# ShiftRegV1_3.net
KiCad netlist of a schematic drawn in EasyEDA
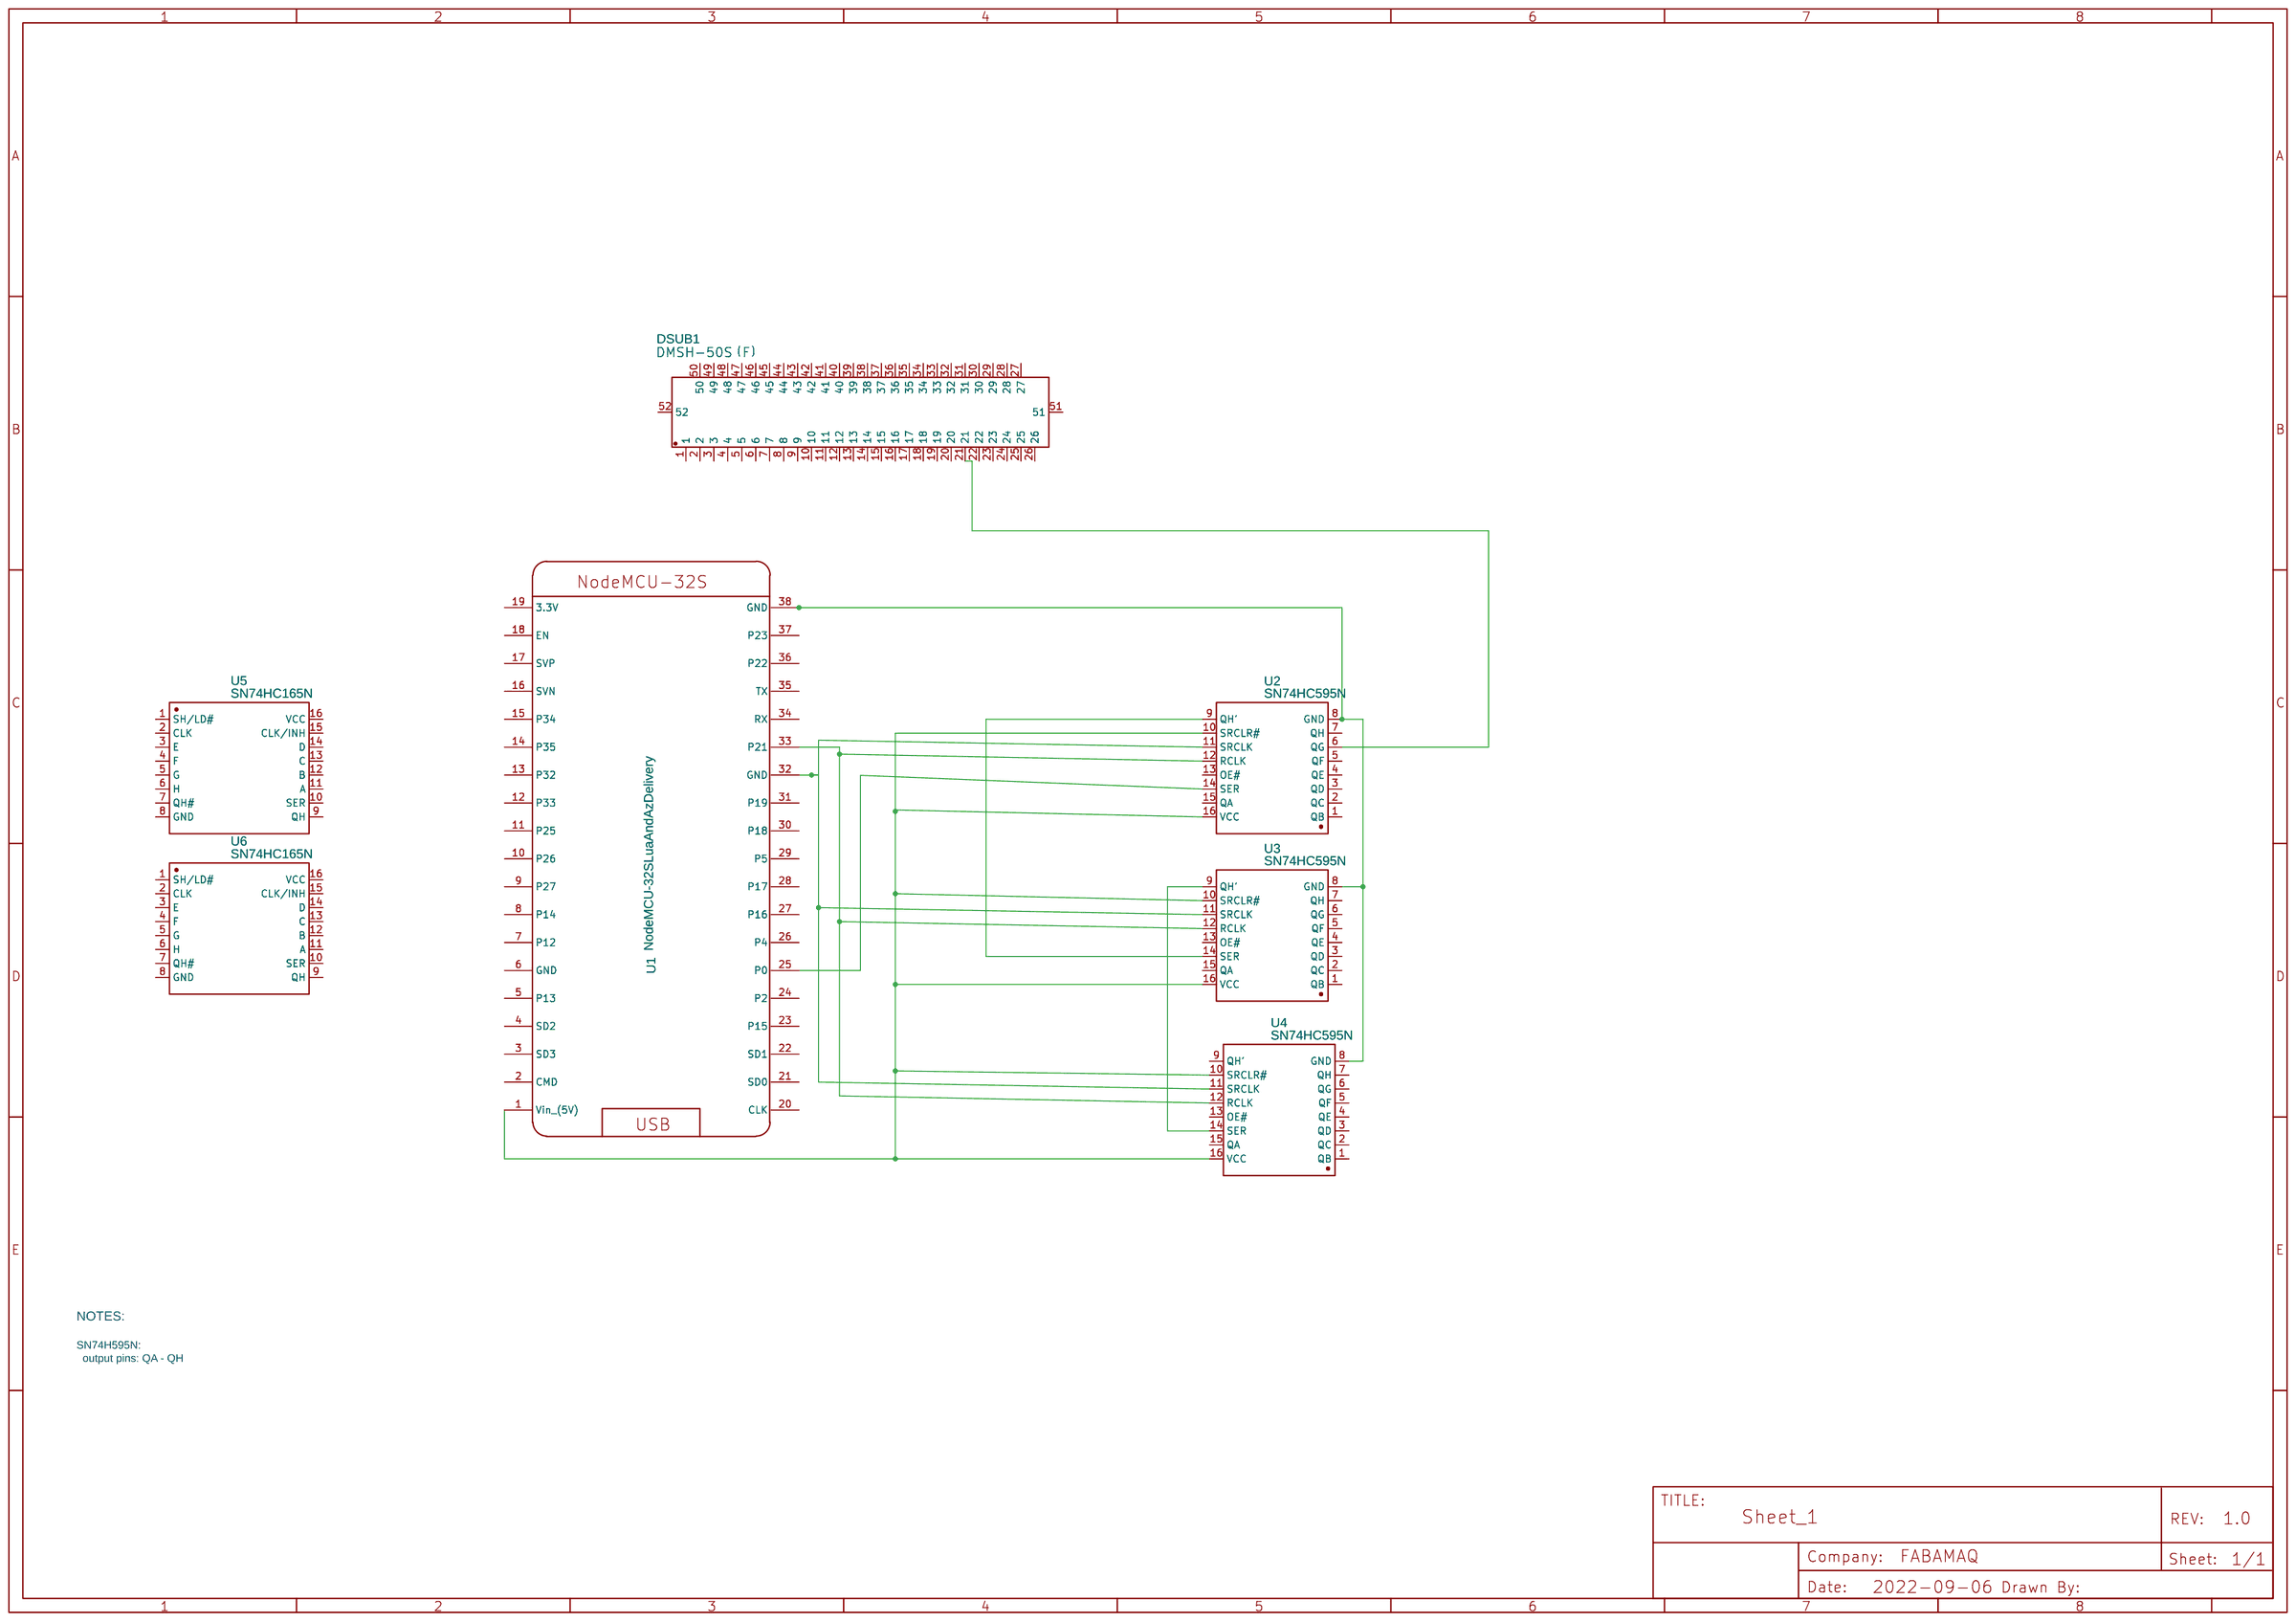
[diagram p0: schematic sheet]

(export (version "E")
  (design (tool "Eeschema 10.0.6"))
  (components
    (comp (ref "DSUB1")
      (value "DMSH-50S（F）")
      (fields (field (name "BOM_Supplier Part") "C98869"))
      (libsource (lib "") (part "DMSH-50S（F）"))
    )
    (comp (ref "U1")
      (value "NodeMCU-32SLuaAndAzDelivery")
      (fields
        (field (name "BOM_Manufacturer Part") "NodeMCU-32SLua")
        (field (name "BOM_Supplier Part") "C111436")
      )
      (libsource (lib "") (part "NodeMCU-32SLuaAndAzDelivery"))
    )
    (comp (ref "U2")
      (value "SN74HC595N")
      (fields (field (name "BOM_Supplier Part") "C78711"))
      (libsource (lib "") (part "SN74HC595N"))
    )
    (comp (ref "U3")
      (value "SN74HC595N")
      (fields (field (name "BOM_Supplier Part") "C78711"))
      (libsource (lib "") (part "SN74HC595N"))
    )
    (comp (ref "U4")
      (value "SN74HC595N")
      (fields (field (name "BOM_Supplier Part") "C78711"))
      (libsource (lib "") (part "SN74HC595N"))
    )
    (comp (ref "U5")
      (value "SN74HC165N")
      (fields (field (name "BOM_Supplier Part") "C2909"))
      (libsource (lib "") (part "SN74HC165N"))
    )
    (comp (ref "U6")
      (value "SN74HC165N")
      (fields (field (name "BOM_Supplier Part") "C2909"))
      (libsource (lib "") (part "SN74HC165N"))
    )
  )
  (nets
    (net (code "1") (name "Net-(U1-P0)") (class "Default")
      (node (ref "U1") (pin "25") (pinfunction "P0_25") (pintype "unspecified"))
      (node (ref "U2") (pin "14") (pinfunction "SER_14") (pintype "unspecified"))
    )
    (net (code "2") (name "Net-(U1-P21)") (class "Default")
      (node (ref "U1") (pin "33") (pinfunction "P21_33") (pintype "unspecified"))
      (node (ref "U2") (pin "12") (pinfunction "RCLK_12") (pintype "unspecified"))
      (node (ref "U3") (pin "12") (pinfunction "RCLK_12") (pintype "unspecified"))
      (node (ref "U4") (pin "12") (pinfunction "RCLK_12") (pintype "unspecified"))
    )
    (net (code "3") (name "Net-(U1-Vin_(5V))") (class "Default")
      (node (ref "U1") (pin "1") (pinfunction "Vin_(5V)_1") (pintype "unspecified"))
      (node (ref "U2") (pin "10") (pinfunction "SRCLR#_10") (pintype "unspecified"))
      (node (ref "U2") (pin "16") (pinfunction "VCC_16") (pintype "unspecified"))
      (node (ref "U3") (pin "10") (pinfunction "SRCLR#_10") (pintype "unspecified"))
      (node (ref "U3") (pin "16") (pinfunction "VCC_16") (pintype "unspecified"))
      (node (ref "U4") (pin "10") (pinfunction "SRCLR#_10") (pintype "unspecified"))
      (node (ref "U4") (pin "16") (pinfunction "VCC_16") (pintype "unspecified"))
    )
    (net (code "4") (name "Net-(U2-GND)") (class "Default")
      (node (ref "U1") (pin "38") (pinfunction "GND_38") (pintype "unspecified"))
      (node (ref "U2") (pin "8") (pinfunction "GND_8") (pintype "unspecified"))
      (node (ref "U3") (pin "8") (pinfunction "GND_8") (pintype "unspecified"))
      (node (ref "U4") (pin "8") (pinfunction "GND_8") (pintype "unspecified"))
    )
    (net (code "5") (name "Net-(U2-QG)") (class "Default")
      (node (ref "DSUB1") (pin "21") (pinfunction "21_21") (pintype "unspecified"))
      (node (ref "U2") (pin "6") (pinfunction "QG_6") (pintype "unspecified"))
    )
    (net (code "6") (name "Net-(U2-QH')") (class "Default")
      (node (ref "U2") (pin "9") (pinfunction "QH'_9") (pintype "unspecified"))
      (node (ref "U3") (pin "14") (pinfunction "SER_14") (pintype "unspecified"))
    )
    (net (code "7") (name "Net-(U2-SRCLK)") (class "Default")
      (node (ref "U1") (pin "32") (pinfunction "GND_32") (pintype "unspecified"))
      (node (ref "U2") (pin "11") (pinfunction "SRCLK_11") (pintype "unspecified"))
      (node (ref "U3") (pin "11") (pinfunction "SRCLK_11") (pintype "unspecified"))
      (node (ref "U4") (pin "11") (pinfunction "SRCLK_11") (pintype "unspecified"))
    )
    (net (code "8") (name "Net-(U3-QH')") (class "Default")
      (node (ref "U3") (pin "9") (pinfunction "QH'_9") (pintype "unspecified"))
      (node (ref "U4") (pin "14") (pinfunction "SER_14") (pintype "unspecified"))
    )
    (net (code "9") (name "unconnected-(DSUB1-Pad1)") (class "Default")
      (node (ref "DSUB1") (pin "1") (pinfunction "1_1") (pintype "unspecified"))
    )
    (net (code "10") (name "unconnected-(DSUB1-Pad2)") (class "Default")
      (node (ref "DSUB1") (pin "2") (pinfunction "2_2") (pintype "unspecified"))
    )
    (net (code "11") (name "unconnected-(DSUB1-Pad3)") (class "Default")
      (node (ref "DSUB1") (pin "3") (pinfunction "3_3") (pintype "unspecified"))
    )
    (net (code "12") (name "unconnected-(DSUB1-Pad4)") (class "Default")
      (node (ref "DSUB1") (pin "4") (pinfunction "4_4") (pintype "unspecified"))
    )
    (net (code "13") (name "unconnected-(DSUB1-Pad5)") (class "Default")
      (node (ref "DSUB1") (pin "5") (pinfunction "5_5") (pintype "unspecified"))
    )
    (net (code "14") (name "unconnected-(DSUB1-Pad6)") (class "Default")
      (node (ref "DSUB1") (pin "6") (pinfunction "6_6") (pintype "unspecified"))
    )
    (net (code "15") (name "unconnected-(DSUB1-Pad7)") (class "Default")
      (node (ref "DSUB1") (pin "7") (pinfunction "7_7") (pintype "unspecified"))
    )
    (net (code "16") (name "unconnected-(DSUB1-Pad8)") (class "Default")
      (node (ref "DSUB1") (pin "8") (pinfunction "8_8") (pintype "unspecified"))
    )
    (net (code "17") (name "unconnected-(DSUB1-Pad9)") (class "Default")
      (node (ref "DSUB1") (pin "9") (pinfunction "9_9") (pintype "unspecified"))
    )
    (net (code "18") (name "unconnected-(DSUB1-Pad10)") (class "Default")
      (node (ref "DSUB1") (pin "10") (pinfunction "10_10") (pintype "unspecified"))
    )
    (net (code "19") (name "unconnected-(DSUB1-Pad11)") (class "Default")
      (node (ref "DSUB1") (pin "11") (pinfunction "11_11") (pintype "unspecified"))
    )
    (net (code "20") (name "unconnected-(DSUB1-Pad12)") (class "Default")
      (node (ref "DSUB1") (pin "12") (pinfunction "12_12") (pintype "unspecified"))
    )
    (net (code "21") (name "unconnected-(DSUB1-Pad13)") (class "Default")
      (node (ref "DSUB1") (pin "13") (pinfunction "13_13") (pintype "unspecified"))
    )
    (net (code "22") (name "unconnected-(DSUB1-Pad14)") (class "Default")
      (node (ref "DSUB1") (pin "14") (pinfunction "14_14") (pintype "unspecified"))
    )
    (net (code "23") (name "unconnected-(DSUB1-Pad15)") (class "Default")
      (node (ref "DSUB1") (pin "15") (pinfunction "15_15") (pintype "unspecified"))
    )
    (net (code "24") (name "unconnected-(DSUB1-Pad16)") (class "Default")
      (node (ref "DSUB1") (pin "16") (pinfunction "16_16") (pintype "unspecified"))
    )
    (net (code "25") (name "unconnected-(DSUB1-Pad17)") (class "Default")
      (node (ref "DSUB1") (pin "17") (pinfunction "17_17") (pintype "unspecified"))
    )
    (net (code "26") (name "unconnected-(DSUB1-Pad18)") (class "Default")
      (node (ref "DSUB1") (pin "18") (pinfunction "18_18") (pintype "unspecified"))
    )
    (net (code "27") (name "unconnected-(DSUB1-Pad19)") (class "Default")
      (node (ref "DSUB1") (pin "19") (pinfunction "19_19") (pintype "unspecified"))
    )
    (net (code "28") (name "unconnected-(DSUB1-Pad20)") (class "Default")
      (node (ref "DSUB1") (pin "20") (pinfunction "20_20") (pintype "unspecified"))
    )
    (net (code "29") (name "unconnected-(DSUB1-Pad22)") (class "Default")
      (node (ref "DSUB1") (pin "22") (pinfunction "22_22") (pintype "unspecified"))
    )
    (net (code "30") (name "unconnected-(DSUB1-Pad23)") (class "Default")
      (node (ref "DSUB1") (pin "23") (pinfunction "23_23") (pintype "unspecified"))
    )
    (net (code "31") (name "unconnected-(DSUB1-Pad24)") (class "Default")
      (node (ref "DSUB1") (pin "24") (pinfunction "24_24") (pintype "unspecified"))
    )
    (net (code "32") (name "unconnected-(DSUB1-Pad25)") (class "Default")
      (node (ref "DSUB1") (pin "25") (pinfunction "25_25") (pintype "unspecified"))
    )
    (net (code "33") (name "unconnected-(DSUB1-Pad26)") (class "Default")
      (node (ref "DSUB1") (pin "26") (pinfunction "26_26") (pintype "unspecified"))
    )
    (net (code "34") (name "unconnected-(DSUB1-Pad27)") (class "Default")
      (node (ref "DSUB1") (pin "27") (pinfunction "27_27") (pintype "unspecified"))
    )
    (net (code "35") (name "unconnected-(DSUB1-Pad28)") (class "Default")
      (node (ref "DSUB1") (pin "28") (pinfunction "28_28") (pintype "unspecified"))
    )
    (net (code "36") (name "unconnected-(DSUB1-Pad29)") (class "Default")
      (node (ref "DSUB1") (pin "29") (pinfunction "29_29") (pintype "unspecified"))
    )
    (net (code "37") (name "unconnected-(DSUB1-Pad30)") (class "Default")
      (node (ref "DSUB1") (pin "30") (pinfunction "30_30") (pintype "unspecified"))
    )
    (net (code "38") (name "unconnected-(DSUB1-Pad31)") (class "Default")
      (node (ref "DSUB1") (pin "31") (pinfunction "31_31") (pintype "unspecified"))
    )
    (net (code "39") (name "unconnected-(DSUB1-Pad32)") (class "Default")
      (node (ref "DSUB1") (pin "32") (pinfunction "32_32") (pintype "unspecified"))
    )
    (net (code "40") (name "unconnected-(DSUB1-Pad33)") (class "Default")
      (node (ref "DSUB1") (pin "33") (pinfunction "33_33") (pintype "unspecified"))
    )
    (net (code "41") (name "unconnected-(DSUB1-Pad34)") (class "Default")
      (node (ref "DSUB1") (pin "34") (pinfunction "34_34") (pintype "unspecified"))
    )
    (net (code "42") (name "unconnected-(DSUB1-Pad35)") (class "Default")
      (node (ref "DSUB1") (pin "35") (pinfunction "35_35") (pintype "unspecified"))
    )
    (net (code "43") (name "unconnected-(DSUB1-Pad36)") (class "Default")
      (node (ref "DSUB1") (pin "36") (pinfunction "36_36") (pintype "unspecified"))
    )
    (net (code "44") (name "unconnected-(DSUB1-Pad37)") (class "Default")
      (node (ref "DSUB1") (pin "37") (pinfunction "37_37") (pintype "unspecified"))
    )
    (net (code "45") (name "unconnected-(DSUB1-Pad38)") (class "Default")
      (node (ref "DSUB1") (pin "38") (pinfunction "38_38") (pintype "unspecified"))
    )
    (net (code "46") (name "unconnected-(DSUB1-Pad39)") (class "Default")
      (node (ref "DSUB1") (pin "39") (pinfunction "39_39") (pintype "unspecified"))
    )
    (net (code "47") (name "unconnected-(DSUB1-Pad40)") (class "Default")
      (node (ref "DSUB1") (pin "40") (pinfunction "40_40") (pintype "unspecified"))
    )
    (net (code "48") (name "unconnected-(DSUB1-Pad41)") (class "Default")
      (node (ref "DSUB1") (pin "41") (pinfunction "41_41") (pintype "unspecified"))
    )
    (net (code "49") (name "unconnected-(DSUB1-Pad42)") (class "Default")
      (node (ref "DSUB1") (pin "42") (pinfunction "42_42") (pintype "unspecified"))
    )
    (net (code "50") (name "unconnected-(DSUB1-Pad43)") (class "Default")
      (node (ref "DSUB1") (pin "43") (pinfunction "43_43") (pintype "unspecified"))
    )
    (net (code "51") (name "unconnected-(DSUB1-Pad44)") (class "Default")
      (node (ref "DSUB1") (pin "44") (pinfunction "44_44") (pintype "unspecified"))
    )
    (net (code "52") (name "unconnected-(DSUB1-Pad45)") (class "Default")
      (node (ref "DSUB1") (pin "45") (pinfunction "45_45") (pintype "unspecified"))
    )
    (net (code "53") (name "unconnected-(DSUB1-Pad46)") (class "Default")
      (node (ref "DSUB1") (pin "46") (pinfunction "46_46") (pintype "unspecified"))
    )
    (net (code "54") (name "unconnected-(DSUB1-Pad47)") (class "Default")
      (node (ref "DSUB1") (pin "47") (pinfunction "47_47") (pintype "unspecified"))
    )
    (net (code "55") (name "unconnected-(DSUB1-Pad48)") (class "Default")
      (node (ref "DSUB1") (pin "48") (pinfunction "48_48") (pintype "unspecified"))
    )
    (net (code "56") (name "unconnected-(DSUB1-Pad49)") (class "Default")
      (node (ref "DSUB1") (pin "49") (pinfunction "49_49") (pintype "unspecified"))
    )
    (net (code "57") (name "unconnected-(DSUB1-Pad50)") (class "Default")
      (node (ref "DSUB1") (pin "50") (pinfunction "50_50") (pintype "unspecified"))
    )
    (net (code "58") (name "unconnected-(DSUB1-Pad51)") (class "Default")
      (node (ref "DSUB1") (pin "51") (pinfunction "51_51") (pintype "unspecified"))
    )
    (net (code "59") (name "unconnected-(DSUB1-Pad52)") (class "Default")
      (node (ref "DSUB1") (pin "52") (pinfunction "52_52") (pintype "unspecified"))
    )
    (net (code "60") (name "unconnected-(U1-3.3V-Pad19)") (class "Default")
      (node (ref "U1") (pin "19") (pinfunction "3.3V_19") (pintype "unspecified"))
    )
    (net (code "61") (name "unconnected-(U1-CLK-Pad20)") (class "Default")
      (node (ref "U1") (pin "20") (pinfunction "CLK_20") (pintype "unspecified"))
    )
    (net (code "62") (name "unconnected-(U1-CMD-Pad2)") (class "Default")
      (node (ref "U1") (pin "2") (pinfunction "CMD_2") (pintype "unspecified"))
    )
    (net (code "63") (name "unconnected-(U1-EN-Pad18)") (class "Default")
      (node (ref "U1") (pin "18") (pinfunction "EN_18") (pintype "unspecified"))
    )
    (net (code "64") (name "unconnected-(U1-GND-Pad6)") (class "Default")
      (node (ref "U1") (pin "6") (pinfunction "GND_6") (pintype "unspecified"))
    )
    (net (code "65") (name "unconnected-(U1-P2-Pad24)") (class "Default")
      (node (ref "U1") (pin "24") (pinfunction "P2_24") (pintype "unspecified"))
    )
    (net (code "66") (name "unconnected-(U1-P4-Pad26)") (class "Default")
      (node (ref "U1") (pin "26") (pinfunction "P4_26") (pintype "unspecified"))
    )
    (net (code "67") (name "unconnected-(U1-P5-Pad29)") (class "Default")
      (node (ref "U1") (pin "29") (pinfunction "P5_29") (pintype "unspecified"))
    )
    (net (code "68") (name "unconnected-(U1-P12-Pad7)") (class "Default")
      (node (ref "U1") (pin "7") (pinfunction "P12_7") (pintype "unspecified"))
    )
    (net (code "69") (name "unconnected-(U1-P13-Pad5)") (class "Default")
      (node (ref "U1") (pin "5") (pinfunction "P13_5") (pintype "unspecified"))
    )
    (net (code "70") (name "unconnected-(U1-P14-Pad8)") (class "Default")
      (node (ref "U1") (pin "8") (pinfunction "P14_8") (pintype "unspecified"))
    )
    (net (code "71") (name "unconnected-(U1-P15-Pad23)") (class "Default")
      (node (ref "U1") (pin "23") (pinfunction "P15_23") (pintype "unspecified"))
    )
    (net (code "72") (name "unconnected-(U1-P16-Pad27)") (class "Default")
      (node (ref "U1") (pin "27") (pinfunction "P16_27") (pintype "unspecified"))
    )
    (net (code "73") (name "unconnected-(U1-P17-Pad28)") (class "Default")
      (node (ref "U1") (pin "28") (pinfunction "P17_28") (pintype "unspecified"))
    )
    (net (code "74") (name "unconnected-(U1-P18-Pad30)") (class "Default")
      (node (ref "U1") (pin "30") (pinfunction "P18_30") (pintype "unspecified"))
    )
    (net (code "75") (name "unconnected-(U1-P19-Pad31)") (class "Default")
      (node (ref "U1") (pin "31") (pinfunction "P19_31") (pintype "unspecified"))
    )
    (net (code "76") (name "unconnected-(U1-P22-Pad36)") (class "Default")
      (node (ref "U1") (pin "36") (pinfunction "P22_36") (pintype "unspecified"))
    )
    (net (code "77") (name "unconnected-(U1-P23-Pad37)") (class "Default")
      (node (ref "U1") (pin "37") (pinfunction "P23_37") (pintype "unspecified"))
    )
    (net (code "78") (name "unconnected-(U1-P25-Pad11)") (class "Default")
      (node (ref "U1") (pin "11") (pinfunction "P25_11") (pintype "unspecified"))
    )
    (net (code "79") (name "unconnected-(U1-P26-Pad10)") (class "Default")
      (node (ref "U1") (pin "10") (pinfunction "P26_10") (pintype "unspecified"))
    )
    (net (code "80") (name "unconnected-(U1-P27-Pad9)") (class "Default")
      (node (ref "U1") (pin "9") (pinfunction "P27_9") (pintype "unspecified"))
    )
    (net (code "81") (name "unconnected-(U1-P32-Pad13)") (class "Default")
      (node (ref "U1") (pin "13") (pinfunction "P32_13") (pintype "unspecified"))
    )
    (net (code "82") (name "unconnected-(U1-P33-Pad12)") (class "Default")
      (node (ref "U1") (pin "12") (pinfunction "P33_12") (pintype "unspecified"))
    )
    (net (code "83") (name "unconnected-(U1-P34-Pad15)") (class "Default")
      (node (ref "U1") (pin "15") (pinfunction "P34_15") (pintype "unspecified"))
    )
    (net (code "84") (name "unconnected-(U1-P35-Pad14)") (class "Default")
      (node (ref "U1") (pin "14") (pinfunction "P35_14") (pintype "unspecified"))
    )
    (net (code "85") (name "unconnected-(U1-RX-Pad34)") (class "Default")
      (node (ref "U1") (pin "34") (pinfunction "RX_34") (pintype "unspecified"))
    )
    (net (code "86") (name "unconnected-(U1-SD0-Pad21)") (class "Default")
      (node (ref "U1") (pin "21") (pinfunction "SD0_21") (pintype "unspecified"))
    )
    (net (code "87") (name "unconnected-(U1-SD1-Pad22)") (class "Default")
      (node (ref "U1") (pin "22") (pinfunction "SD1_22") (pintype "unspecified"))
    )
    (net (code "88") (name "unconnected-(U1-SD2-Pad4)") (class "Default")
      (node (ref "U1") (pin "4") (pinfunction "SD2_4") (pintype "unspecified"))
    )
    (net (code "89") (name "unconnected-(U1-SD3-Pad3)") (class "Default")
      (node (ref "U1") (pin "3") (pinfunction "SD3_3") (pintype "unspecified"))
    )
    (net (code "90") (name "unconnected-(U1-SVN-Pad16)") (class "Default")
      (node (ref "U1") (pin "16") (pinfunction "SVN_16") (pintype "unspecified"))
    )
    (net (code "91") (name "unconnected-(U1-SVP-Pad17)") (class "Default")
      (node (ref "U1") (pin "17") (pinfunction "SVP_17") (pintype "unspecified"))
    )
    (net (code "92") (name "unconnected-(U1-TX-Pad35)") (class "Default")
      (node (ref "U1") (pin "35") (pinfunction "TX_35") (pintype "unspecified"))
    )
    (net (code "93") (name "unconnected-(U2-OE#-Pad13)") (class "Default")
      (node (ref "U2") (pin "13") (pinfunction "OE#_13") (pintype "unspecified"))
    )
    (net (code "94") (name "unconnected-(U2-QA-Pad15)") (class "Default")
      (node (ref "U2") (pin "15") (pinfunction "QA_15") (pintype "unspecified"))
    )
    (net (code "95") (name "unconnected-(U2-QB-Pad1)") (class "Default")
      (node (ref "U2") (pin "1") (pinfunction "QB_1") (pintype "unspecified"))
    )
    (net (code "96") (name "unconnected-(U2-QC-Pad2)") (class "Default")
      (node (ref "U2") (pin "2") (pinfunction "QC_2") (pintype "unspecified"))
    )
    (net (code "97") (name "unconnected-(U2-QD-Pad3)") (class "Default")
      (node (ref "U2") (pin "3") (pinfunction "QD_3") (pintype "unspecified"))
    )
    (net (code "98") (name "unconnected-(U2-QE-Pad4)") (class "Default")
      (node (ref "U2") (pin "4") (pinfunction "QE_4") (pintype "unspecified"))
    )
    (net (code "99") (name "unconnected-(U2-QF-Pad5)") (class "Default")
      (node (ref "U2") (pin "5") (pinfunction "QF_5") (pintype "unspecified"))
    )
    (net (code "100") (name "unconnected-(U2-QH-Pad7)") (class "Default")
      (node (ref "U2") (pin "7") (pinfunction "QH_7") (pintype "unspecified"))
    )
    (net (code "101") (name "unconnected-(U3-OE#-Pad13)") (class "Default")
      (node (ref "U3") (pin "13") (pinfunction "OE#_13") (pintype "unspecified"))
    )
    (net (code "102") (name "unconnected-(U3-QA-Pad15)") (class "Default")
      (node (ref "U3") (pin "15") (pinfunction "QA_15") (pintype "unspecified"))
    )
    (net (code "103") (name "unconnected-(U3-QB-Pad1)") (class "Default")
      (node (ref "U3") (pin "1") (pinfunction "QB_1") (pintype "unspecified"))
    )
    (net (code "104") (name "unconnected-(U3-QC-Pad2)") (class "Default")
      (node (ref "U3") (pin "2") (pinfunction "QC_2") (pintype "unspecified"))
    )
    (net (code "105") (name "unconnected-(U3-QD-Pad3)") (class "Default")
      (node (ref "U3") (pin "3") (pinfunction "QD_3") (pintype "unspecified"))
    )
    (net (code "106") (name "unconnected-(U3-QE-Pad4)") (class "Default")
      (node (ref "U3") (pin "4") (pinfunction "QE_4") (pintype "unspecified"))
    )
    (net (code "107") (name "unconnected-(U3-QF-Pad5)") (class "Default")
      (node (ref "U3") (pin "5") (pinfunction "QF_5") (pintype "unspecified"))
    )
    (net (code "108") (name "unconnected-(U3-QG-Pad6)") (class "Default")
      (node (ref "U3") (pin "6") (pinfunction "QG_6") (pintype "unspecified"))
    )
    (net (code "109") (name "unconnected-(U3-QH-Pad7)") (class "Default")
      (node (ref "U3") (pin "7") (pinfunction "QH_7") (pintype "unspecified"))
    )
    (net (code "110") (name "unconnected-(U4-OE#-Pad13)") (class "Default")
      (node (ref "U4") (pin "13") (pinfunction "OE#_13") (pintype "unspecified"))
    )
    (net (code "111") (name "unconnected-(U4-QA-Pad15)") (class "Default")
      (node (ref "U4") (pin "15") (pinfunction "QA_15") (pintype "unspecified"))
    )
    (net (code "112") (name "unconnected-(U4-QB-Pad1)") (class "Default")
      (node (ref "U4") (pin "1") (pinfunction "QB_1") (pintype "unspecified"))
    )
    (net (code "113") (name "unconnected-(U4-QC-Pad2)") (class "Default")
      (node (ref "U4") (pin "2") (pinfunction "QC_2") (pintype "unspecified"))
    )
    (net (code "114") (name "unconnected-(U4-QD-Pad3)") (class "Default")
      (node (ref "U4") (pin "3") (pinfunction "QD_3") (pintype "unspecified"))
    )
    (net (code "115") (name "unconnected-(U4-QE-Pad4)") (class "Default")
      (node (ref "U4") (pin "4") (pinfunction "QE_4") (pintype "unspecified"))
    )
    (net (code "116") (name "unconnected-(U4-QF-Pad5)") (class "Default")
      (node (ref "U4") (pin "5") (pinfunction "QF_5") (pintype "unspecified"))
    )
    (net (code "117") (name "unconnected-(U4-QG-Pad6)") (class "Default")
      (node (ref "U4") (pin "6") (pinfunction "QG_6") (pintype "unspecified"))
    )
    (net (code "118") (name "unconnected-(U4-QH'-Pad9)") (class "Default")
      (node (ref "U4") (pin "9") (pinfunction "QH'_9") (pintype "unspecified"))
    )
    (net (code "119") (name "unconnected-(U4-QH-Pad7)") (class "Default")
      (node (ref "U4") (pin "7") (pinfunction "QH_7") (pintype "unspecified"))
    )
    (net (code "120") (name "unconnected-(U5-A-Pad11)") (class "Default")
      (node (ref "U5") (pin "11") (pinfunction "A_11") (pintype "unspecified"))
    )
    (net (code "121") (name "unconnected-(U5-B-Pad12)") (class "Default")
      (node (ref "U5") (pin "12") (pinfunction "B_12") (pintype "unspecified"))
    )
    (net (code "122") (name "unconnected-(U5-C-Pad13)") (class "Default")
      (node (ref "U5") (pin "13") (pinfunction "C_13") (pintype "unspecified"))
    )
    (net (code "123") (name "unconnected-(U5-CLK-Pad2)") (class "Default")
      (node (ref "U5") (pin "2") (pinfunction "CLK_2") (pintype "unspecified"))
    )
    (net (code "124") (name "unconnected-(U5-CLK{slash}INH-Pad15)") (class "Default")
      (node (ref "U5") (pin "15") (pinfunction "CLK/INH_15") (pintype "unspecified"))
    )
    (net (code "125") (name "unconnected-(U5-D-Pad14)") (class "Default")
      (node (ref "U5") (pin "14") (pinfunction "D_14") (pintype "unspecified"))
    )
    (net (code "126") (name "unconnected-(U5-E-Pad3)") (class "Default")
      (node (ref "U5") (pin "3") (pinfunction "E_3") (pintype "unspecified"))
    )
    (net (code "127") (name "unconnected-(U5-F-Pad4)") (class "Default")
      (node (ref "U5") (pin "4") (pinfunction "F_4") (pintype "unspecified"))
    )
    (net (code "128") (name "unconnected-(U5-G-Pad5)") (class "Default")
      (node (ref "U5") (pin "5") (pinfunction "G_5") (pintype "unspecified"))
    )
    (net (code "129") (name "unconnected-(U5-GND-Pad8)") (class "Default")
      (node (ref "U5") (pin "8") (pinfunction "GND_8") (pintype "unspecified"))
    )
    (net (code "130") (name "unconnected-(U5-H-Pad6)") (class "Default")
      (node (ref "U5") (pin "6") (pinfunction "H_6") (pintype "unspecified"))
    )
    (net (code "131") (name "unconnected-(U5-QH#-Pad7)") (class "Default")
      (node (ref "U5") (pin "7") (pinfunction "QH#_7") (pintype "unspecified"))
    )
    (net (code "132") (name "unconnected-(U5-QH-Pad9)") (class "Default")
      (node (ref "U5") (pin "9") (pinfunction "QH_9") (pintype "unspecified"))
    )
    (net (code "133") (name "unconnected-(U5-SER-Pad10)") (class "Default")
      (node (ref "U5") (pin "10") (pinfunction "SER_10") (pintype "unspecified"))
    )
    (net (code "134") (name "unconnected-(U5-SH{slash}LD#-Pad1)") (class "Default")
      (node (ref "U5") (pin "1") (pinfunction "SH/LD#_1") (pintype "unspecified"))
    )
    (net (code "135") (name "unconnected-(U5-VCC-Pad16)") (class "Default")
      (node (ref "U5") (pin "16") (pinfunction "VCC_16") (pintype "unspecified"))
    )
    (net (code "136") (name "unconnected-(U6-A-Pad11)") (class "Default")
      (node (ref "U6") (pin "11") (pinfunction "A_11") (pintype "unspecified"))
    )
    (net (code "137") (name "unconnected-(U6-B-Pad12)") (class "Default")
      (node (ref "U6") (pin "12") (pinfunction "B_12") (pintype "unspecified"))
    )
    (net (code "138") (name "unconnected-(U6-C-Pad13)") (class "Default")
      (node (ref "U6") (pin "13") (pinfunction "C_13") (pintype "unspecified"))
    )
    (net (code "139") (name "unconnected-(U6-CLK-Pad2)") (class "Default")
      (node (ref "U6") (pin "2") (pinfunction "CLK_2") (pintype "unspecified"))
    )
    (net (code "140") (name "unconnected-(U6-CLK{slash}INH-Pad15)") (class "Default")
      (node (ref "U6") (pin "15") (pinfunction "CLK/INH_15") (pintype "unspecified"))
    )
    (net (code "141") (name "unconnected-(U6-D-Pad14)") (class "Default")
      (node (ref "U6") (pin "14") (pinfunction "D_14") (pintype "unspecified"))
    )
    (net (code "142") (name "unconnected-(U6-E-Pad3)") (class "Default")
      (node (ref "U6") (pin "3") (pinfunction "E_3") (pintype "unspecified"))
    )
    (net (code "143") (name "unconnected-(U6-F-Pad4)") (class "Default")
      (node (ref "U6") (pin "4") (pinfunction "F_4") (pintype "unspecified"))
    )
    (net (code "144") (name "unconnected-(U6-G-Pad5)") (class "Default")
      (node (ref "U6") (pin "5") (pinfunction "G_5") (pintype "unspecified"))
    )
    (net (code "145") (name "unconnected-(U6-GND-Pad8)") (class "Default")
      (node (ref "U6") (pin "8") (pinfunction "GND_8") (pintype "unspecified"))
    )
    (net (code "146") (name "unconnected-(U6-H-Pad6)") (class "Default")
      (node (ref "U6") (pin "6") (pinfunction "H_6") (pintype "unspecified"))
    )
    (net (code "147") (name "unconnected-(U6-QH#-Pad7)") (class "Default")
      (node (ref "U6") (pin "7") (pinfunction "QH#_7") (pintype "unspecified"))
    )
    (net (code "148") (name "unconnected-(U6-QH-Pad9)") (class "Default")
      (node (ref "U6") (pin "9") (pinfunction "QH_9") (pintype "unspecified"))
    )
    (net (code "149") (name "unconnected-(U6-SER-Pad10)") (class "Default")
      (node (ref "U6") (pin "10") (pinfunction "SER_10") (pintype "unspecified"))
    )
    (net (code "150") (name "unconnected-(U6-SH{slash}LD#-Pad1)") (class "Default")
      (node (ref "U6") (pin "1") (pinfunction "SH/LD#_1") (pintype "unspecified"))
    )
    (net (code "151") (name "unconnected-(U6-VCC-Pad16)") (class "Default")
      (node (ref "U6") (pin "16") (pinfunction "VCC_16") (pintype "unspecified"))
    )
  )
)
